# 16V3_EDA.net
KiCad netlist of a schematic drawn in EasyEDA Pro
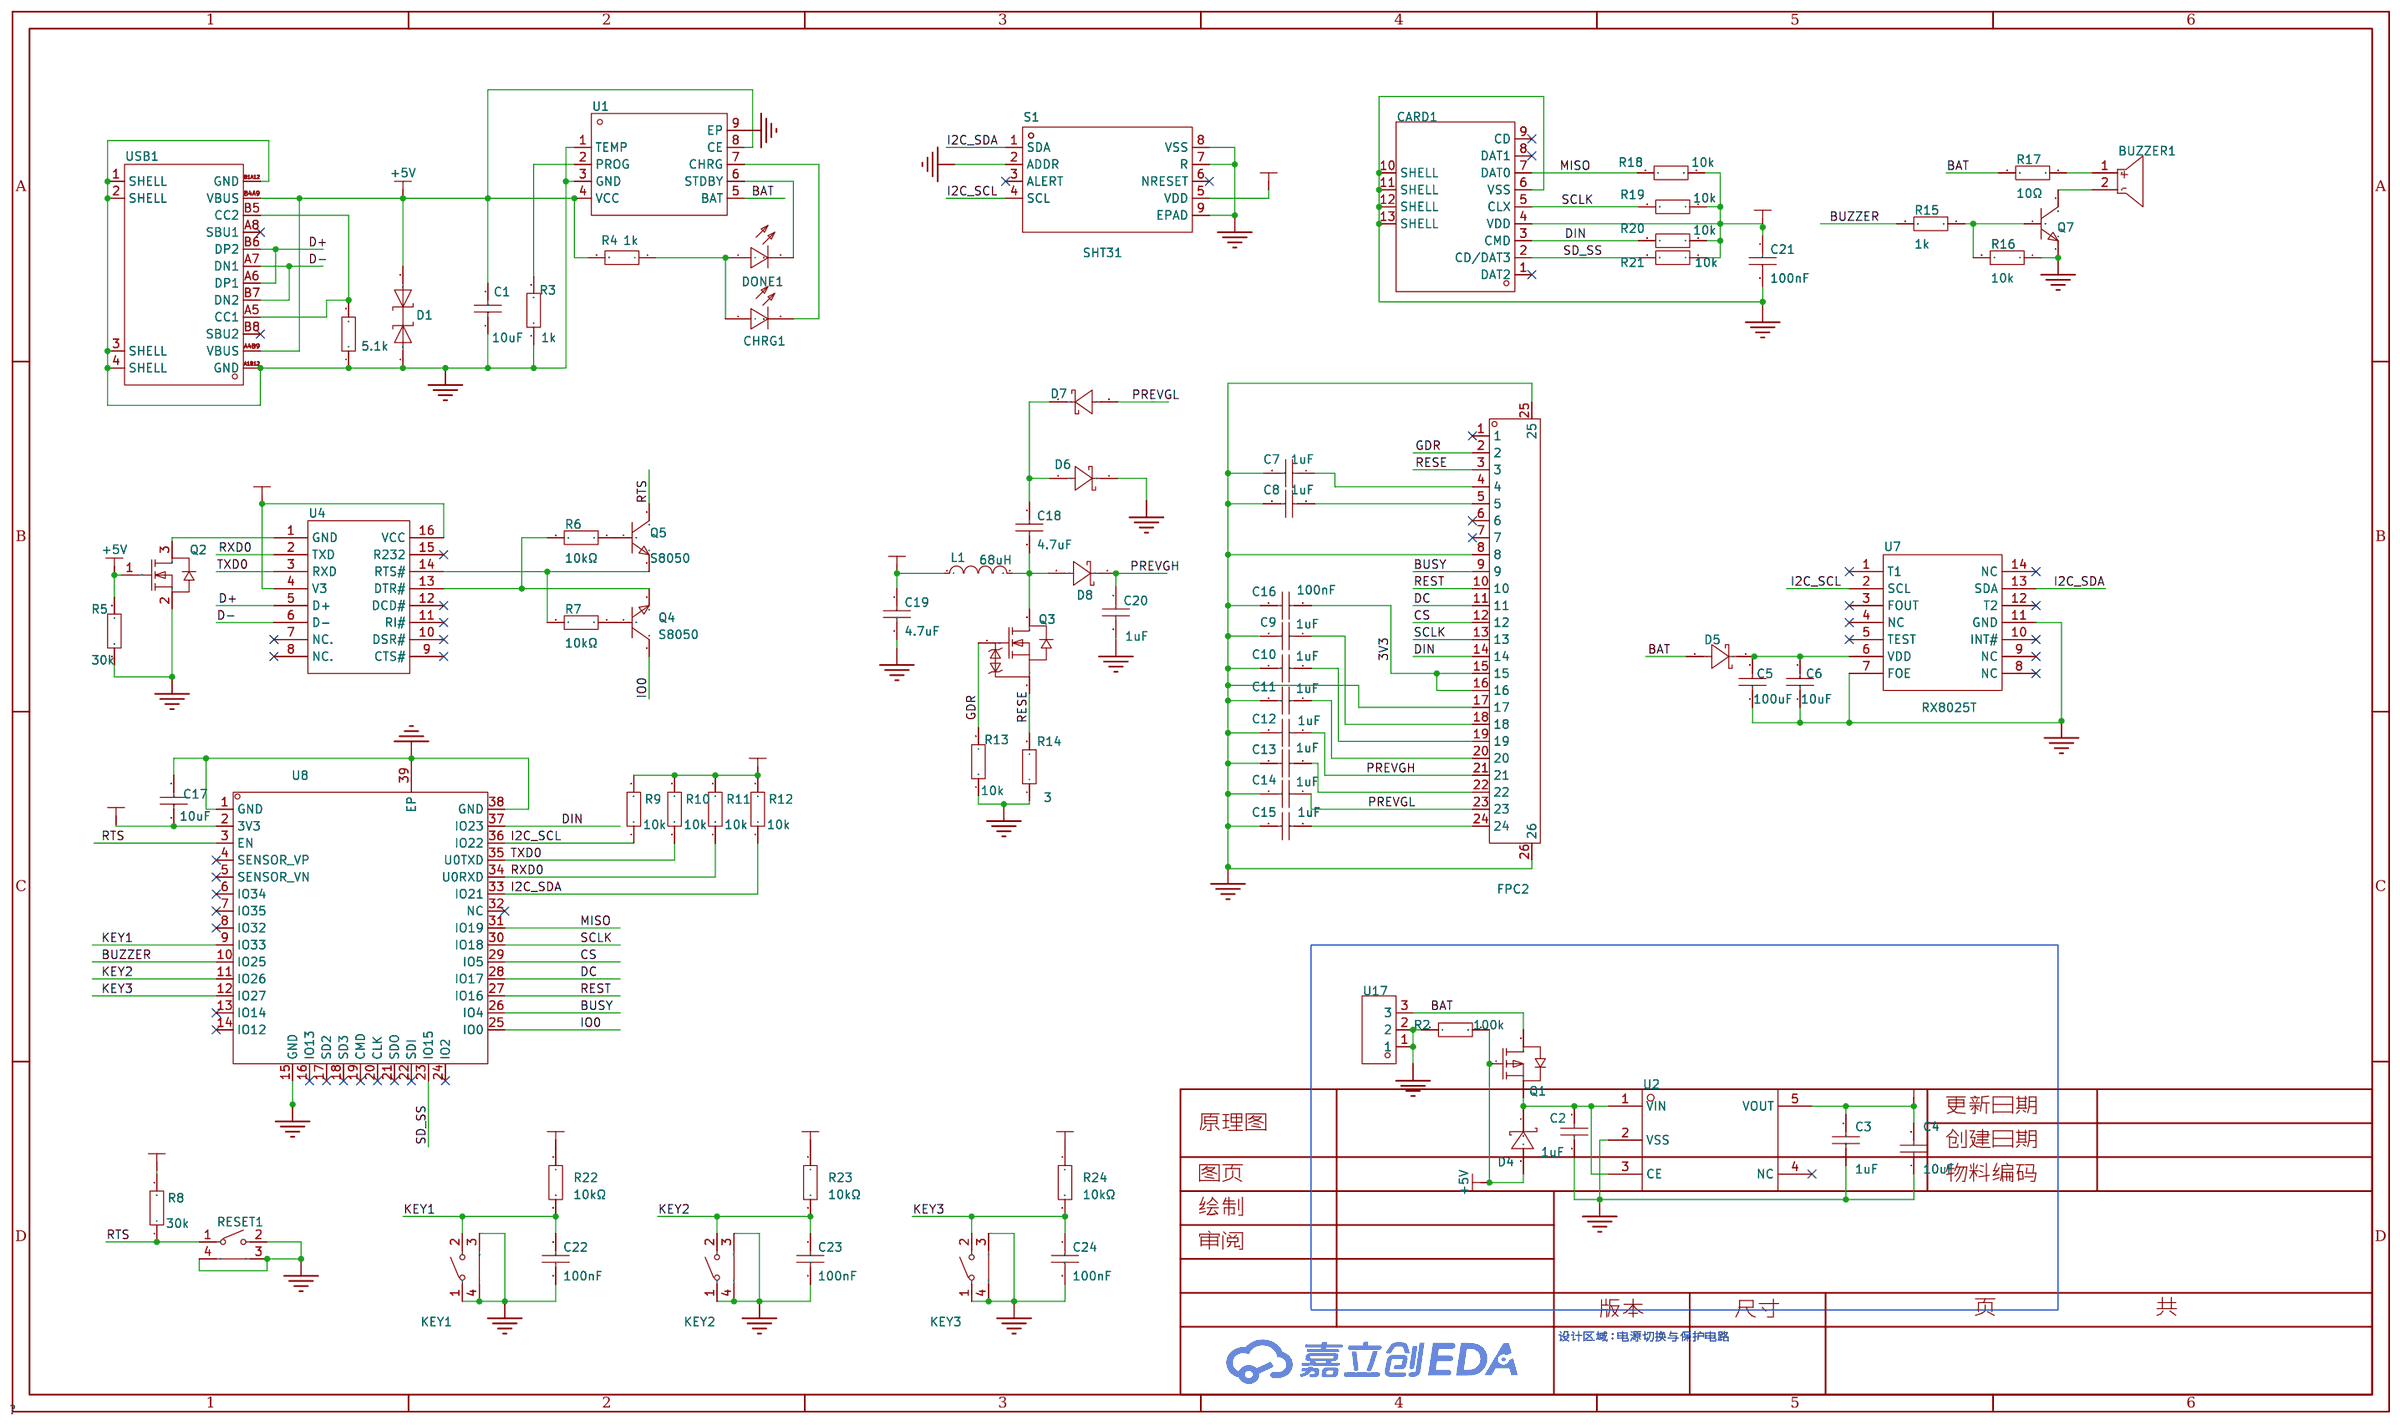
[diagram p0: schematic sheet]

(export (version "E")
  (design (tool "Eeschema 10.0.6"))
  (components
    (comp (ref "BUZZER1")
      (value "FMQ-BUZZER2")
      (footprint "easyedapro:BUZ-TH_BD12.0-P7.60-D0.6-FD")
      (libsource (lib "easyedapro") (part "FMQ-BUZZER2"))
    )
    (comp (ref "C1")
      (value "10uF")
      (footprint "easyedapro:C0805")
      (fields
        (field (name "Manufacturer Part") "CC0805KRX7R9BB104")
        (field (name "Manufacturer") "YAGEO(国巨)")
      )
      (libsource (lib "easyedapro") (part "CC0805KRX7R9BB104"))
    )
    (comp (ref "C2")
      (value "1uF")
      (footprint "easyedapro:C0805")
      (fields
        (field (name "Manufacturer Part") "CC0805KRX7R9BB104")
        (field (name "Manufacturer") "YAGEO(国巨)")
      )
      (libsource (lib "easyedapro") (part "CC0805KRX7R9BB104"))
    )
    (comp (ref "C3")
      (value "1uF")
      (footprint "easyedapro:C0805")
      (fields
        (field (name "Manufacturer Part") "CC0805KRX7R9BB104")
        (field (name "Manufacturer") "YAGEO(国巨)")
      )
      (libsource (lib "easyedapro") (part "CC0805KRX7R9BB104"))
    )
    (comp (ref "C4")
      (value "10uF")
      (footprint "easyedapro:C0805")
      (fields
        (field (name "Manufacturer Part") "CC0805KRX7R9BB104")
        (field (name "Manufacturer") "YAGEO(国巨)")
      )
      (libsource (lib "easyedapro") (part "CC0805KRX7R9BB104"))
    )
    (comp (ref "C5")
      (value "100uF")
      (footprint "easyedapro:C0805")
      (description "容值:100nF;精度:±10%;额定电压:50V;温度系数:X7R;")
      (fields
        (field (name "Manufacturer Part") "CC0805KRX7R9BB104")
        (field (name "Manufacturer") "YAGEO(国巨)")
      )
      (libsource (lib "easyedapro") (part "CC0805KRX7R9BB104"))
    )
    (comp (ref "C6")
      (value "10uF")
      (footprint "easyedapro:C0805")
      (fields
        (field (name "Manufacturer Part") "CC0805KRX7R9BB104")
        (field (name "Manufacturer") "YAGEO(国巨)")
      )
      (libsource (lib "easyedapro") (part "CC0805KRX7R9BB104"))
    )
    (comp (ref "C7")
      (value "1uF")
      (footprint "easyedapro:C0805")
      (fields
        (field (name "Manufacturer Part") "CC0805KRX7R9BB104")
        (field (name "Manufacturer") "YAGEO(国巨)")
      )
      (libsource (lib "easyedapro") (part "CC0805KRX7R9BB104"))
    )
    (comp (ref "C8")
      (value "1uF")
      (footprint "easyedapro:C0805")
      (fields
        (field (name "Manufacturer Part") "CC0805KRX7R9BB104")
        (field (name "Manufacturer") "YAGEO(国巨)")
      )
      (libsource (lib "easyedapro") (part "CC0805KRX7R9BB104"))
    )
    (comp (ref "C9")
      (value "1uF")
      (footprint "easyedapro:C0805")
      (fields
        (field (name "Manufacturer Part") "CC0805KRX7R9BB104")
        (field (name "Manufacturer") "YAGEO(国巨)")
      )
      (libsource (lib "easyedapro") (part "CC0805KRX7R9BB104"))
    )
    (comp (ref "C10")
      (value "1uF")
      (footprint "easyedapro:C0805")
      (fields
        (field (name "Manufacturer Part") "CC0805KRX7R9BB104")
        (field (name "Manufacturer") "YAGEO(国巨)")
      )
      (libsource (lib "easyedapro") (part "CC0805KRX7R9BB104"))
    )
    (comp (ref "C11")
      (value "1uF")
      (footprint "easyedapro:C0805")
      (fields
        (field (name "Manufacturer Part") "CC0805KRX7R9BB104")
        (field (name "Manufacturer") "YAGEO(国巨)")
      )
      (libsource (lib "easyedapro") (part "CC0805KRX7R9BB104"))
    )
    (comp (ref "C12")
      (value "1uF")
      (footprint "easyedapro:C0805")
      (fields
        (field (name "Manufacturer Part") "CC0805KRX7R9BB104")
        (field (name "Manufacturer") "YAGEO(国巨)")
      )
      (libsource (lib "easyedapro") (part "CC0805KRX7R9BB104"))
    )
    (comp (ref "C13")
      (value "1uF")
      (footprint "easyedapro:C0805")
      (fields
        (field (name "Manufacturer Part") "CC0805KRX7R9BB104")
        (field (name "Manufacturer") "YAGEO(国巨)")
      )
      (libsource (lib "easyedapro") (part "CC0805KRX7R9BB104"))
    )
    (comp (ref "C14")
      (value "1uF")
      (footprint "easyedapro:C0805")
      (fields
        (field (name "Manufacturer Part") "CC0805KRX7R9BB104")
        (field (name "Manufacturer") "YAGEO(国巨)")
      )
      (libsource (lib "easyedapro") (part "CC0805KRX7R9BB104"))
    )
    (comp (ref "C15")
      (value "1uF")
      (footprint "easyedapro:C0805")
      (fields
        (field (name "Manufacturer Part") "CC0805KRX7R9BB104")
        (field (name "Manufacturer") "YAGEO(国巨)")
      )
      (libsource (lib "easyedapro") (part "CC0805KRX7R9BB104"))
    )
    (comp (ref "C16")
      (value "100nF")
      (footprint "easyedapro:C0805")
      (description "容值:100nF;精度:±10%;额定电压:50V;温度系数:X7R;")
      (fields
        (field (name "Manufacturer Part") "CC0805KRX7R9BB104")
        (field (name "Manufacturer") "YAGEO(国巨)")
      )
      (libsource (lib "easyedapro") (part "CC0805KRX7R9BB104"))
    )
    (comp (ref "C17")
      (value "10uF")
      (footprint "easyedapro:C0805")
      (fields
        (field (name "Manufacturer Part") "CC0805KRX7R9BB104")
        (field (name "Manufacturer") "YAGEO(国巨)")
      )
      (libsource (lib "easyedapro") (part "CC0805KRX7R9BB104"))
    )
    (comp (ref "C18")
      (value "4.7uF")
      (footprint "easyedapro:C0805")
      (description "容值:100nF;精度:±10%;额定电压:50V;温度系数:X7R;")
      (fields
        (field (name "Manufacturer Part") "CC0805KRX7R9BB104")
        (field (name "Manufacturer") "YAGEO(国巨)")
      )
      (libsource (lib "easyedapro") (part "CC0805KRX7R9BB104"))
    )
    (comp (ref "C19")
      (value "4.7uF")
      (footprint "easyedapro:C0805")
      (fields
        (field (name "Manufacturer Part") "CC0805KRX7R9BB104")
        (field (name "Manufacturer") "YAGEO(国巨)")
      )
      (libsource (lib "easyedapro") (part "CC0805KRX7R9BB104"))
    )
    (comp (ref "C20")
      (value "1uF")
      (footprint "easyedapro:C0805")
      (fields
        (field (name "Manufacturer Part") "CC0805KRX7R9BB104")
        (field (name "Manufacturer") "YAGEO(国巨)")
      )
      (libsource (lib "easyedapro") (part "CC0805KRX7R9BB104"))
    )
    (comp (ref "C21")
      (value "100nF")
      (footprint "easyedapro:C0805")
      (description "容值:100nF;精度:±10%;额定电压:50V;温度系数:X7R;")
      (fields
        (field (name "Manufacturer Part") "CC0805KRX7R9BB104")
        (field (name "Manufacturer") "YAGEO(国巨)")
      )
      (libsource (lib "easyedapro") (part "CC0805KRX7R9BB104"))
    )
    (comp (ref "C22")
      (value "100nF")
      (footprint "easyedapro:C0805")
      (fields
        (field (name "Manufacturer Part") "CC0805KRX7R9BB104")
        (field (name "Manufacturer") "YAGEO(国巨)")
      )
      (libsource (lib "easyedapro") (part "CC0805KRX7R9BB104"))
    )
    (comp (ref "C23")
      (value "100nF")
      (footprint "easyedapro:C0805")
      (fields
        (field (name "Manufacturer Part") "CC0805KRX7R9BB104")
        (field (name "Manufacturer") "YAGEO(国巨)")
      )
      (libsource (lib "easyedapro") (part "CC0805KRX7R9BB104"))
    )
    (comp (ref "C24")
      (value "100nF")
      (footprint "easyedapro:C0805")
      (fields
        (field (name "Manufacturer Part") "CC0805KRX7R9BB104")
        (field (name "Manufacturer") "YAGEO(国巨)")
      )
      (libsource (lib "easyedapro") (part "CC0805KRX7R9BB104"))
    )
    (comp (ref "CARD1")
      (value "~")
      (footprint "easyedapro:TF-SMD_THD2528-11SD-GF")
      (description "卡连接方式:自弹式;卡类型:MicroSD卡(TF卡);连接器类型:卡座;本体最大高度:2mm;工作温度范围:-;")
      (fields (field (name "Manufacturer Part") "THD2528-11SD-GF") (field (name "Manufacturer") "THD(台华达)"))
      (libsource (lib "easyedapro") (part "THD2528-11SD-GF"))
    )
    (comp (ref "CHRG1")
      (value "~")
      (footprint "easyedapro:LED0603-R-RD")
      (fields
        (field (name "Manufacturer Part") "19-217/R6C-AL1M2VY/3T")
        (field (name "Manufacturer") "EVERLIGHT(台湾亿光)")
      )
      (libsource (lib "easyedapro") (part "19-217/R6C-AL1M2VY/3T"))
    )
    (comp (ref "D1")
      (value "~")
      (footprint "easyedapro:SOD-523_L1.2-W0.8-LS1.6-BI")
      (description "极性:双向;反向截止电压(Vrwm):5V@(最大值);击穿电压(最小值):5.6V;峰值脉冲电流(Ipp)@10/1000s:4A;最大钳位电压:12V;")
      (fields (field (name "Manufacturer Part") "ESD5Z5.0VC") (field (name "Manufacturer") "TC(德昌)"))
      (libsource (lib "easyedapro") (part "ESD5Z5.0VC"))
    )
    (comp (ref "D4")
      (value "~")
      (footprint "easyedapro:SMA_L4.3-W2.6-LS5.1-RD")
      (description "直流反向耐压(Vr):40V;平均整流电流(Io):3A;正向压降(Vf):550mV@3A;")
      (fields (field (name "Manufacturer Part") "SS34") (field (name "Manufacturer") "SINO-IC(光宇睿芯)"))
      (libsource (lib "easyedapro") (part "SS34_C355267"))
    )
    (comp (ref "D5")
      (value "~")
      (footprint "easyedapro:SOD-123_L2.7-W1.6-LS3.7-RD-1")
      (description "直流反向耐压(Vr):30V;平均整流电流(Io):500mA;正向压降(Vf):550mV@500mA;")
      (fields (field (name "Manufacturer Part") "MBR0530") (field (name "Manufacturer") "YANGJIE(扬杰)"))
      (libsource (lib "easyedapro") (part "MBR0530_C699108"))
    )
    (comp (ref "D6")
      (value "~")
      (footprint "easyedapro:SOD-123_L2.7-W1.6-LS3.7-RD-1")
      (description "直流反向耐压(Vr):30V;平均整流电流(Io):500mA;正向压降(Vf):550mV@500mA;")
      (fields (field (name "Manufacturer Part") "MBR0530") (field (name "Manufacturer") "YANGJIE(扬杰)"))
      (libsource (lib "easyedapro") (part "MBR0530_C699108"))
    )
    (comp (ref "D7")
      (value "~")
      (footprint "easyedapro:SOD-123_L2.7-W1.6-LS3.7-RD-1")
      (description "直流反向耐压(Vr):30V;平均整流电流(Io):500mA;正向压降(Vf):550mV@500mA;")
      (fields (field (name "Manufacturer Part") "MBR0530") (field (name "Manufacturer") "YANGJIE(扬杰)"))
      (libsource (lib "easyedapro") (part "MBR0530_C699108"))
    )
    (comp (ref "D8")
      (value "~")
      (footprint "easyedapro:SOD-123_L2.7-W1.6-LS3.7-RD-1")
      (description "直流反向耐压(Vr):30V;平均整流电流(Io):500mA;正向压降(Vf):550mV@500mA;")
      (fields (field (name "Manufacturer Part") "MBR0530") (field (name "Manufacturer") "YANGJIE(扬杰)"))
      (libsource (lib "easyedapro") (part "MBR0530_C699108"))
    )
    (comp (ref "DONE1")
      (value "~")
      (footprint "easyedapro:LED0603-R-RD")
      (fields
        (field (name "Manufacturer Part") "19-217/R6C-AL1M2VY/3T")
        (field (name "Manufacturer") "EVERLIGHT(台湾亿光)")
      )
      (libsource (lib "easyedapro") (part "19-217/R6C-AL1M2VY/3T"))
    )
    (comp (ref "FPC2")
      (value "~")
      (footprint "easyedapro:FPC-SMD_24P-L17.5-W5.4-P0.50")
      (description "间距:0.5mm;触点数量:24;锁定特性:抽屉式;安装类型:卧贴;触点类型:上接;")
      (fields (field (name "Manufacturer Part") "AFC07-S24ECC-00") (field (name "Manufacturer") "JS(钜硕电子)"))
      (libsource (lib "easyedapro") (part "FPC 0.5MM 24P Pull type H2.0mm Pick up"))
    )
    (comp (ref "KEY1")
      (value "~")
      (footprint "easyedapro:SW-SMD_L4.7-W3.5-P3.35-EH")
      (fields
        (field (name "Manufacturer Part") "GT-TC018B-H0375-L1")
        (field (name "Manufacturer") "G-Switch(品赞)")
      )
      (libsource (lib "easyedapro") (part "GT-TC018B-H0375-L1"))
    )
    (comp (ref "KEY2")
      (value "~")
      (footprint "easyedapro:SW-SMD_L4.7-W3.5-P3.35-EH")
      (fields
        (field (name "Manufacturer Part") "GT-TC018B-H0375-L1")
        (field (name "Manufacturer") "G-Switch(品赞)")
      )
      (libsource (lib "easyedapro") (part "GT-TC018B-H0375-L1"))
    )
    (comp (ref "KEY3")
      (value "~")
      (footprint "easyedapro:SW-SMD_L4.7-W3.5-P3.35-EH")
      (fields
        (field (name "Manufacturer Part") "GT-TC018B-H0375-L1")
        (field (name "Manufacturer") "G-Switch(品赞)")
      )
      (libsource (lib "easyedapro") (part "GT-TC018B-H0375-L1"))
    )
    (comp (ref "L1")
      (value "68uH")
      (footprint "easyedapro:IND-SMD_L4.0-W4.0")
      (description "电感值:68uH;精度:±20%;额定电流:-;直流电阻(DCR):-;")
      (fields (field (name "Manufacturer Part") "CR4020-680M") (field (name "Manufacturer") "ceaiya(柯爱亚)"))
      (libsource (lib "easyedapro") (part "CR4020-680M"))
    )
    (comp (ref "Q1")
      (value "~")
      (footprint "easyedapro:SOT-23_L2.9-W1.3-P1.90-LS2.4-BR")
      (fields (field (name "Manufacturer Part") "SI2305") (field (name "Manufacturer") "BORN伯恩半导体"))
      (libsource (lib "easyedapro") (part "SI2305_C344006"))
    )
    (comp (ref "Q2")
      (value "~")
      (footprint "easyedapro:SOT-23_L2.9-W1.3-P1.90-LS2.4-BR")
      (fields (field (name "Manufacturer Part") "AO3402") (field (name "Manufacturer") "GOODWORK(固得沃克)"))
      (libsource (lib "easyedapro") (part "AO3402_C2938369"))
    )
    (comp (ref "Q3")
      (value "~")
      (footprint "easyedapro:SOT-323_L2.0-W1.3-P1.30-LS2.1-BR")
      (fields
        (field (name "Manufacturer Part") "SI1308EDL-T1-GE3")
        (field (name "Manufacturer") "VISHAY(威世)")
      )
      (libsource (lib "easyedapro") (part "SI1308EDL-T1-GE3"))
    )
    (comp (ref "Q4")
      (value "S8050")
      (footprint "easyedapro:SOT-23-3_L3.0-W1.7-P0.95-LS2.9-BR")
      (fields (field (name "Manufacturer") "CJ"))
      (libsource (lib "") (part "S8050_1"))
    )
    (comp (ref "Q5")
      (value "S8050")
      (footprint "easyedapro:SOT-23-3_L3.0-W1.7-P0.95-LS2.9-BR(1)")
      (fields (field (name "Manufacturer") "CJ"))
      (libsource (lib "easyedapro") (part "S8050"))
    )
    (comp (ref "Q7")
      (value "S8050-J3Y")
      (footprint "easyedapro:SOT-23-3_L3.0-W1.7-P0.95-LS2.9-BR")
      (fields (field (name "Manufacturer") "(MDD) Jiangsu Yutai Elec"))
      (libsource (lib "easyedapro") (part "S8050-J3Y"))
    )
    (comp (ref "R1")
      (value "5.1k")
      (footprint "easyedapro:R0603")
      (description "电阻类型:薄膜电阻;阻值:10k;精度:±0.1%;功率:100mW;温度系数:±25ppm/;最大工作电压:75V;工作温度范围:-55~+155;")
      (fields
        (field (name "Manufacturer Part") "TR0603B10K0P0525Z")
        (field (name "Manufacturer") "EVER OHMS(天二科技)")
      )
      (libsource (lib "easyedapro") (part "TR0603B10KP05250.1W"))
    )
    (comp (ref "R2")
      (value "100k")
      (footprint "easyedapro:R0603")
      (description "电阻类型:薄膜电阻;阻值:10k;精度:±0.1%;功率:100mW;温度系数:±25ppm/;最大工作电压:75V;工作温度范围:-55~+155;")
      (fields
        (field (name "Manufacturer Part") "TR0603B10K0P0525Z")
        (field (name "Manufacturer") "EVER OHMS(天二科技)")
      )
      (libsource (lib "easyedapro") (part "TR0603B10KP05250.1W"))
    )
    (comp (ref "R3")
      (value "1k")
      (footprint "easyedapro:R0603")
      (description "电阻类型:薄膜电阻;阻值:10k;精度:±0.1%;功率:100mW;温度系数:±25ppm/;最大工作电压:75V;工作温度范围:-55~+155;")
      (fields
        (field (name "Manufacturer Part") "TR0603B10K0P0525Z")
        (field (name "Manufacturer") "EVER OHMS(天二科技)")
      )
      (libsource (lib "easyedapro") (part "TR0603B10KP05250.1W"))
    )
    (comp (ref "R4")
      (value "1k")
      (footprint "easyedapro:R0603")
      (description "电阻类型:薄膜电阻;阻值:10k;精度:±0.1%;功率:100mW;温度系数:±25ppm/;最大工作电压:75V;工作温度范围:-55~+155;")
      (fields
        (field (name "Manufacturer Part") "TR0603B10K0P0525Z")
        (field (name "Manufacturer") "EVER OHMS(天二科技)")
      )
      (libsource (lib "easyedapro") (part "TR0603B10KP05250.1W"))
    )
    (comp (ref "R5")
      (value "30k")
      (footprint "easyedapro:R0603")
      (description "电阻类型:薄膜电阻;阻值:10k;精度:±0.1%;功率:100mW;温度系数:±25ppm/;最大工作电压:75V;工作温度范围:-55~+155;")
      (fields
        (field (name "Manufacturer Part") "TR0603B10K0P0525Z")
        (field (name "Manufacturer") "EVER OHMS(天二科技)")
      )
      (libsource (lib "easyedapro") (part "TR0603B10KP05250.1W"))
    )
    (comp (ref "R6")
      (value "10kΩ")
      (footprint "easyedapro:R0603")
      (description "电阻类型:薄膜电阻;阻值:10k;精度:±0.1%;功率:100mW;温度系数:±25ppm/;最大工作电压:75V;工作温度范围:-55~+155;")
      (fields
        (field (name "Manufacturer Part") "TR0603B10K0P0525Z")
        (field (name "Manufacturer") "EVER OHMS(天二科技)")
      )
      (libsource (lib "easyedapro") (part "TR0603B10KP05250.1W"))
    )
    (comp (ref "R7")
      (value "10kΩ")
      (footprint "easyedapro:R0603")
      (description "电阻类型:薄膜电阻;阻值:10k;精度:±0.1%;功率:100mW;温度系数:±25ppm/;最大工作电压:75V;工作温度范围:-55~+155;")
      (fields
        (field (name "Manufacturer Part") "TR0603B10K0P0525Z")
        (field (name "Manufacturer") "EVER OHMS(天二科技)")
      )
      (libsource (lib "easyedapro") (part "TR0603B10KP05250.1W"))
    )
    (comp (ref "R8")
      (value "30k")
      (footprint "easyedapro:R0603")
      (description "电阻类型:薄膜电阻;阻值:10k;精度:±0.1%;功率:100mW;温度系数:±25ppm/;最大工作电压:75V;工作温度范围:-55~+155;")
      (fields
        (field (name "Manufacturer Part") "TR0603B10K0P0525Z")
        (field (name "Manufacturer") "EVER OHMS(天二科技)")
      )
      (libsource (lib "easyedapro") (part "TR0603B10KP05250.1W"))
    )
    (comp (ref "R9")
      (value "10k")
      (footprint "easyedapro:R0603")
      (description "电阻类型:薄膜电阻;阻值:10k;精度:±0.1%;功率:100mW;温度系数:±25ppm/;最大工作电压:75V;工作温度范围:-55~+155;")
      (fields
        (field (name "Manufacturer Part") "TR0603B10K0P0525Z")
        (field (name "Manufacturer") "EVER OHMS(天二科技)")
      )
      (libsource (lib "easyedapro") (part "TR0603B10KP05250.1W"))
    )
    (comp (ref "R10")
      (value "10k")
      (footprint "easyedapro:R0603")
      (description "电阻类型:薄膜电阻;阻值:10k;精度:±0.1%;功率:100mW;温度系数:±25ppm/;最大工作电压:75V;工作温度范围:-55~+155;")
      (fields
        (field (name "Manufacturer Part") "TR0603B10K0P0525Z")
        (field (name "Manufacturer") "EVER OHMS(天二科技)")
      )
      (libsource (lib "easyedapro") (part "TR0603B10KP05250.1W"))
    )
    (comp (ref "R11")
      (value "10k")
      (footprint "easyedapro:R0603")
      (description "电阻类型:薄膜电阻;阻值:10k;精度:±0.1%;功率:100mW;温度系数:±25ppm/;最大工作电压:75V;工作温度范围:-55~+155;")
      (fields
        (field (name "Manufacturer Part") "TR0603B10K0P0525Z")
        (field (name "Manufacturer") "EVER OHMS(天二科技)")
      )
      (libsource (lib "easyedapro") (part "TR0603B10KP05250.1W"))
    )
    (comp (ref "R12")
      (value "10k")
      (footprint "easyedapro:R0603")
      (description "电阻类型:薄膜电阻;阻值:10k;精度:±0.1%;功率:100mW;温度系数:±25ppm/;最大工作电压:75V;工作温度范围:-55~+155;")
      (fields
        (field (name "Manufacturer Part") "TR0603B10K0P0525Z")
        (field (name "Manufacturer") "EVER OHMS(天二科技)")
      )
      (libsource (lib "easyedapro") (part "TR0603B10KP05250.1W"))
    )
    (comp (ref "R13")
      (value "10k")
      (footprint "easyedapro:R0603")
      (description "电阻类型:薄膜电阻;阻值:10k;精度:±0.1%;功率:100mW;温度系数:±25ppm/;最大工作电压:75V;工作温度范围:-55~+155;")
      (fields
        (field (name "Manufacturer Part") "TR0603B10K0P0525Z")
        (field (name "Manufacturer") "EVER OHMS(天二科技)")
      )
      (libsource (lib "easyedapro") (part "TR0603B10KP05250.1W"))
    )
    (comp (ref "R14")
      (value "3")
      (footprint "easyedapro:R0603")
      (description "电阻类型:薄膜电阻;阻值:10k;精度:±0.1%;功率:100mW;温度系数:±25ppm/;最大工作电压:75V;工作温度范围:-55~+155;")
      (fields
        (field (name "Manufacturer Part") "TR0603B10K0P0525Z")
        (field (name "Manufacturer") "EVER OHMS(天二科技)")
      )
      (libsource (lib "easyedapro") (part "TR0603B10KP05250.1W"))
    )
    (comp (ref "R15")
      (value "1k")
      (footprint "easyedapro:R0603")
      (description "电阻类型:薄膜电阻;阻值:10k;精度:±0.1%;功率:100mW;温度系数:±25ppm/;最大工作电压:75V;工作温度范围:-55~+155;")
      (fields
        (field (name "Manufacturer Part") "TR0603B10K0P0525Z")
        (field (name "Manufacturer") "EVER OHMS(天二科技)")
      )
      (libsource (lib "easyedapro") (part "TR0603B10KP05250.1W"))
    )
    (comp (ref "R16")
      (value "10k")
      (footprint "easyedapro:R0603")
      (description "电阻类型:薄膜电阻;阻值:10k;精度:±0.1%;功率:100mW;温度系数:±25ppm/;最大工作电压:75V;工作温度范围:-55~+155;")
      (fields
        (field (name "Manufacturer Part") "TR0603B10K0P0525Z")
        (field (name "Manufacturer") "EVER OHMS(天二科技)")
      )
      (libsource (lib "easyedapro") (part "TR0603B10KP05250.1W"))
    )
    (comp (ref "R17")
      (value "10Ω")
      (footprint "easyedapro:R0603")
      (description "电阻类型:厚膜电阻;阻值:10Ω;精度:±1%;功率:100mW;")
      (fields
        (field (name "Manufacturer Part") "0603WAF100JT5E")
        (field (name "Manufacturer") "UNI-ROYAL(厚声)")
      )
      (libsource (lib "easyedapro") (part "0603WAF100JT5E"))
    )
    (comp (ref "R18")
      (value "10k")
      (footprint "easyedapro:R0603")
      (description "电阻类型:薄膜电阻;阻值:10k;精度:±0.1%;功率:100mW;温度系数:±25ppm/;最大工作电压:75V;工作温度范围:-55~+155;")
      (fields
        (field (name "Manufacturer Part") "TR0603B10K0P0525Z")
        (field (name "Manufacturer") "EVER OHMS(天二科技)")
      )
      (libsource (lib "easyedapro") (part "TR0603B10KP05250.1W"))
    )
    (comp (ref "R19")
      (value "10k")
      (footprint "easyedapro:R0603")
      (description "电阻类型:薄膜电阻;阻值:10k;精度:±0.1%;功率:100mW;温度系数:±25ppm/;最大工作电压:75V;工作温度范围:-55~+155;")
      (fields
        (field (name "Manufacturer Part") "TR0603B10K0P0525Z")
        (field (name "Manufacturer") "EVER OHMS(天二科技)")
      )
      (libsource (lib "easyedapro") (part "TR0603B10KP05250.1W"))
    )
    (comp (ref "R20")
      (value "10k")
      (footprint "easyedapro:R0603")
      (description "电阻类型:薄膜电阻;阻值:10k;精度:±0.1%;功率:100mW;温度系数:±25ppm/;最大工作电压:75V;工作温度范围:-55~+155;")
      (fields
        (field (name "Manufacturer Part") "TR0603B10K0P0525Z")
        (field (name "Manufacturer") "EVER OHMS(天二科技)")
      )
      (libsource (lib "easyedapro") (part "TR0603B10KP05250.1W"))
    )
    (comp (ref "R21")
      (value "10k")
      (footprint "easyedapro:R0603")
      (description "电阻类型:薄膜电阻;阻值:10k;精度:±0.1%;功率:100mW;温度系数:±25ppm/;最大工作电压:75V;工作温度范围:-55~+155;")
      (fields
        (field (name "Manufacturer Part") "TR0603B10K0P0525Z")
        (field (name "Manufacturer") "EVER OHMS(天二科技)")
      )
      (libsource (lib "easyedapro") (part "TR0603B10KP05250.1W"))
    )
    (comp (ref "R22")
      (value "10kΩ")
      (footprint "easyedapro:R0603")
      (description "电阻类型:薄膜电阻;阻值:10k;精度:±0.1%;功率:100mW;温度系数:±25ppm/;最大工作电压:75V;工作温度范围:-55~+155;")
      (fields
        (field (name "Manufacturer Part") "TR0603B10K0P0525Z")
        (field (name "Manufacturer") "EVER OHMS(天二科技)")
      )
      (libsource (lib "easyedapro") (part "TR0603B10KP05250.1W"))
    )
    (comp (ref "R23")
      (value "10kΩ")
      (footprint "easyedapro:R0603")
      (description "电阻类型:薄膜电阻;阻值:10k;精度:±0.1%;功率:100mW;温度系数:±25ppm/;最大工作电压:75V;工作温度范围:-55~+155;")
      (fields
        (field (name "Manufacturer Part") "TR0603B10K0P0525Z")
        (field (name "Manufacturer") "EVER OHMS(天二科技)")
      )
      (libsource (lib "easyedapro") (part "TR0603B10KP05250.1W"))
    )
    (comp (ref "R24")
      (value "10kΩ")
      (footprint "easyedapro:R0603")
      (description "电阻类型:薄膜电阻;阻值:10k;精度:±0.1%;功率:100mW;温度系数:±25ppm/;最大工作电压:75V;工作温度范围:-55~+155;")
      (fields
        (field (name "Manufacturer Part") "TR0603B10K0P0525Z")
        (field (name "Manufacturer") "EVER OHMS(天二科技)")
      )
      (libsource (lib "easyedapro") (part "TR0603B10KP05250.1W"))
    )
    (comp (ref "RESET1")
      (value "~")
      (footprint "easyedapro:SW-SMD_L4.7-W3.5-P3.35-EH")
      (fields
        (field (name "Manufacturer Part") "GT-TC018B-H0375-L1")
        (field (name "Manufacturer") "G-Switch(品赞)")
      )
      (libsource (lib "easyedapro") (part "GT-TC018B-H0375-L1"))
    )
    (comp (ref "S1")
      (value "SHT31")
      (footprint "easyedapro:DFN-8_L2.5-W2.5-P0.50-BL-EP")
      (description "1-101386-01")
      (fields (field (name "Manufacturer") "Sensirion(瑞士盛思锐)"))
      (libsource (lib "easyedapro") (part "SHT31-DIS-B"))
    )
    (comp (ref "U1")
      (value "~")
      (footprint "easyedapro:ESOP-8_L4.9-W3.9-P1.27-LS6.0-BL-EP")
      (description "充电电池的类型:-;电池单元组数:-;最大充电电流:-;充满的电池组电压:-;最大供应电压:-;")
      (fields (field (name "Manufacturer Part") "TP4056") (field (name "Manufacturer") "UMW(友台半导体)"))
      (libsource (lib "easyedapro") (part "TP4056_C725790"))
    )
    (comp (ref "U2") (value "~") (libsource (lib "easyedapro") (part "LDO")))
    (comp (ref "U4")
      (value "~")
      (footprint "easyedapro:SOP-16_L10.0-W3.9-P1.27-LS6.0-BL")
      (description "类型:Transceiver;协议类别:USB 2.0;驱动器/接收器数:-;数据速率:2Mbps;")
      (fields (field (name "Manufacturer Part") "CH340C") (field (name "Manufacturer") "WCH(南京沁恒)"))
      (libsource (lib "easyedapro") (part "CH340C"))
    )
    (comp (ref "U7")
      (value "RX8025T")
      (footprint "easyedapro:SOIC-14_L10.0-W5.5-P1.27-LS7.8-BL")
      (description "时钟芯片类型:Clock/Calendar;存储器容量:-;时间格式:HH:MM:SS;日期格式:YY-MM-DD;接口类型:I2C;")
      (fields (field (name "Manufacturer Part") "RX8025T-UB") (field (name "Manufacturer") "EPSON(爱普生)"))
      (libsource (lib "easyedapro") (part "RX8025T-UB"))
    )
    (comp (ref "U8")
      (value "~")
      (footprint "easyedapro:WIRELM-SMD_ESP32-S")
      (fields (field (name "Manufacturer Part") "ESP32-S") (field (name "Manufacturer") "Ai-Thinker(安信可)"))
      (libsource (lib "easyedapro") (part "ESP32-S"))
    )
    (comp (ref "U17")
      (value "ZX-XH2.54-3PZZ")
      (footprint "easyedapro:CONN-TH_3P-P2.54_2501S-3P")
      (fields (field (name "Manufacturer") "Megastar(兆星)"))
      (libsource (lib "easyedapro") (part "ZX-XH2.54-3PZZ"))
    )
    (comp (ref "USB1")
      (value "~")
      (footprint "easyedapro:USB-SMD_TYPE-611S-T3")
      (description "连接器类型:Type-C;标准:-;公母:母座;触点数量:16;端口数量:1;安装方式:卧贴;额定电流 - 电源:3A;工作温度范围:-25~+85;")
      (fields (field (name "Manufacturer Part") "TYPE-611S-T3") (field (name "Manufacturer") "Yuandi(台湾元迪)"))
      (libsource (lib "easyedapro") (part "TYPE-611S-T3"))
    )
  )
  (nets
    (net (code "1") (name "+5V") (class "Default")
      (node (ref "C1") (pin "2") (pinfunction "2_2") (pintype "input"))
      (node (ref "D1") (pin "2") (pinfunction "2_2") (pintype "input"))
      (node (ref "D4") (pin "2") (pinfunction "A_2") (pintype "input"))
      (node (ref "Q1") (pin "1") (pinfunction "G_1") (pintype "input"))
      (node (ref "Q2") (pin "1") (pinfunction "G_1") (pintype "input"))
      (node (ref "R2") (pin "2") (pinfunction "2_2") (pintype "input"))
      (node (ref "R4") (pin "2") (pinfunction "2_2") (pintype "input"))
      (node (ref "R5") (pin "2") (pinfunction "2_2") (pintype "input"))
      (node (ref "U1") (pin "4") (pinfunction "VCC_4") (pintype "input"))
      (node (ref "U1") (pin "8") (pinfunction "CE_8") (pintype "input"))
      (node (ref "USB1") (pin "A4B9") (pinfunction "VBUS_A4B9") (pintype "input"))
      (node (ref "USB1") (pin "B4A9") (pinfunction "VBUS_B4A9") (pintype "input"))
    )
    (net (code "2") (name "/BAT") (class "Default")
      (node (ref "D5") (pin "2") (pinfunction "A_2") (pintype "input"))
      (node (ref "Q1") (pin "3") (pinfunction "D_3") (pintype "input"))
      (node (ref "R17") (pin "1") (pinfunction "1_1") (pintype "input"))
      (node (ref "U1") (pin "5") (pinfunction "BAT_5") (pintype "input"))
      (node (ref "U17") (pin "3") (pinfunction "3_3") (pintype "unspecified"))
    )
    (net (code "3") (name "/BUSY") (class "Default")
      (node (ref "FPC2") (pin "9") (pinfunction "9_9") (pintype "input"))
      (node (ref "U8") (pin "26") (pinfunction "IO4_26") (pintype "input"))
    )
    (net (code "4") (name "/BUZZER") (class "Default")
      (node (ref "R15") (pin "2") (pinfunction "2_2") (pintype "input"))
      (node (ref "U8") (pin "10") (pinfunction "IO25_10") (pintype "input"))
    )
    (net (code "5") (name "/CS") (class "Default")
      (node (ref "FPC2") (pin "12") (pinfunction "12_12") (pintype "input"))
      (node (ref "U8") (pin "29") (pinfunction "IO5_29") (pintype "input"))
    )
    (net (code "6") (name "/D+") (class "Default")
      (node (ref "U4") (pin "5") (pinfunction "D+_5") (pintype "input"))
      (node (ref "USB1") (pin "A6") (pinfunction "DP1_A6") (pintype "input"))
      (node (ref "USB1") (pin "B6") (pinfunction "DP2_B6") (pintype "input"))
    )
    (net (code "7") (name "/D-") (class "Default")
      (node (ref "U4") (pin "6") (pinfunction "D-_6") (pintype "input"))
      (node (ref "USB1") (pin "A7") (pinfunction "DN1_A7") (pintype "input"))
      (node (ref "USB1") (pin "B7") (pinfunction "DN2_B7") (pintype "input"))
    )
    (net (code "8") (name "/DC") (class "Default")
      (node (ref "FPC2") (pin "11") (pinfunction "11_11") (pintype "input"))
      (node (ref "U8") (pin "28") (pinfunction "IO17_28") (pintype "input"))
    )
    (net (code "9") (name "/DIN") (class "Default")
      (node (ref "CARD1") (pin "3") (pinfunction "CMD_3") (pintype "input"))
      (node (ref "FPC2") (pin "14") (pinfunction "14_14") (pintype "input"))
      (node (ref "R20") (pin "2") (pinfunction "2_2") (pintype "input"))
      (node (ref "U8") (pin "37") (pinfunction "IO23_37") (pintype "input"))
    )
    (net (code "10") (name "/GDR") (class "Default")
      (node (ref "FPC2") (pin "2") (pinfunction "2_2") (pintype "input"))
      (node (ref "Q3") (pin "1") (pinfunction "G_1") (pintype "input"))
      (node (ref "R13") (pin "2") (pinfunction "2_2") (pintype "input"))
    )
    (net (code "11") (name "/I2C_SCL") (class "Default")
      (node (ref "R9") (pin "1") (pinfunction "1_1") (pintype "input"))
      (node (ref "S1") (pin "4") (pinfunction "SCL_4") (pintype "unspecified"))
      (node (ref "U7") (pin "2") (pinfunction "SCL_2") (pintype "input"))
      (node (ref "U8") (pin "36") (pinfunction "IO22_36") (pintype "input"))
    )
    (net (code "12") (name "/I2C_SDA") (class "Default")
      (node (ref "R12") (pin "1") (pinfunction "1_1") (pintype "input"))
      (node (ref "S1") (pin "1") (pinfunction "SDA_1") (pintype "unspecified"))
      (node (ref "U7") (pin "13") (pinfunction "SDA_13") (pintype "input"))
      (node (ref "U8") (pin "33") (pinfunction "IO21_33") (pintype "input"))
    )
    (net (code "13") (name "/IO0") (class "Default")
      (node (ref "Q4") (pin "3") (pinfunction "C_3") (pintype "input"))
      (node (ref "U8") (pin "25") (pinfunction "IO0_25") (pintype "input"))
    )
    (net (code "14") (name "/KEY1") (class "Default")
      (node (ref "C22") (pin "1") (pinfunction "1_1") (pintype "input"))
      (node (ref "KEY1") (pin "2") (pinfunction "2_2") (pintype "input"))
      (node (ref "R22") (pin "2") (pinfunction "2_2") (pintype "input"))
      (node (ref "U8") (pin "9") (pinfunction "IO33_9") (pintype "input"))
    )
    (net (code "15") (name "/KEY2") (class "Default")
      (node (ref "C23") (pin "1") (pinfunction "1_1") (pintype "input"))
      (node (ref "KEY2") (pin "2") (pinfunction "2_2") (pintype "input"))
      (node (ref "R23") (pin "2") (pinfunction "2_2") (pintype "input"))
      (node (ref "U8") (pin "11") (pinfunction "IO26_11") (pintype "input"))
    )
    (net (code "16") (name "/KEY3") (class "Default")
      (node (ref "C24") (pin "1") (pinfunction "1_1") (pintype "input"))
      (node (ref "KEY3") (pin "2") (pinfunction "2_2") (pintype "input"))
      (node (ref "R24") (pin "2") (pinfunction "2_2") (pintype "input"))
      (node (ref "U8") (pin "12") (pinfunction "IO27_12") (pintype "input"))
    )
    (net (code "17") (name "/MISO") (class "Default")
      (node (ref "CARD1") (pin "7") (pinfunction "DAT0_7") (pintype "input"))
      (node (ref "R18") (pin "2") (pinfunction "2_2") (pintype "input"))
      (node (ref "U8") (pin "31") (pinfunction "IO19_31") (pintype "input"))
    )
    (net (code "18") (name "/PREVGH") (class "Default")
      (node (ref "C12") (pin "1") (pinfunction "1_1") (pintype "input"))
      (node (ref "C20") (pin "1") (pinfunction "1_1") (pintype "input"))
      (node (ref "D8") (pin "1") (pinfunction "K_1") (pintype "input"))
      (node (ref "FPC2") (pin "21") (pinfunction "21_21") (pintype "input"))
    )
    (net (code "19") (name "/PREVGL") (class "Default")
      (node (ref "C14") (pin "1") (pinfunction "1_1") (pintype "input"))
      (node (ref "D7") (pin "2") (pinfunction "A_2") (pintype "input"))
      (node (ref "FPC2") (pin "23") (pinfunction "23_23") (pintype "input"))
    )
    (net (code "20") (name "/RESE") (class "Default")
      (node (ref "FPC2") (pin "3") (pinfunction "3_3") (pintype "input"))
      (node (ref "Q3") (pin "2") (pinfunction "S_2") (pintype "input"))
      (node (ref "R14") (pin "2") (pinfunction "2_2") (pintype "input"))
    )
    (net (code "21") (name "/REST") (class "Default")
      (node (ref "FPC2") (pin "10") (pinfunction "10_10") (pintype "input"))
      (node (ref "U8") (pin "27") (pinfunction "IO16_27") (pintype "input"))
    )
    (net (code "22") (name "/RTS") (class "Default")
      (node (ref "Q5") (pin "3") (pinfunction "C_3") (pintype "input"))
      (node (ref "R8") (pin "1") (pinfunction "1_1") (pintype "input"))
      (node (ref "RESET1") (pin "1") (pinfunction "1_1") (pintype "input"))
      (node (ref "U8") (pin "3") (pinfunction "EN_3") (pintype "input"))
    )
    (net (code "23") (name "/RXD0") (class "Default")
      (node (ref "R11") (pin "1") (pinfunction "1_1") (pintype "input"))
      (node (ref "U4") (pin "2") (pinfunction "TXD_2") (pintype "input"))
      (node (ref "U8") (pin "34") (pinfunction "U0RXD_34") (pintype "input"))
    )
    (net (code "24") (name "/SCLK") (class "Default")
      (node (ref "CARD1") (pin "5") (pinfunction "CLX_5") (pintype "input"))
      (node (ref "FPC2") (pin "13") (pinfunction "13_13") (pintype "input"))
      (node (ref "R19") (pin "2") (pinfunction "2_2") (pintype "input"))
      (node (ref "U8") (pin "30") (pinfunction "IO18_30") (pintype "input"))
    )
    (net (code "25") (name "/SD_SS") (class "Default")
      (node (ref "CARD1") (pin "2") (pinfunction "CD/DAT3_2") (pintype "input"))
      (node (ref "R21") (pin "2") (pinfunction "2_2") (pintype "input"))
      (node (ref "U8") (pin "23") (pinfunction "IO15_23") (pintype "input"))
    )
    (net (code "26") (name "/TXD0") (class "Default")
      (node (ref "R10") (pin "1") (pinfunction "1_1") (pintype "input"))
      (node (ref "U4") (pin "3") (pinfunction "RXD_3") (pintype "input"))
      (node (ref "U8") (pin "35") (pinfunction "U0TXD_35") (pintype "input"))
    )
    (net (code "27") (name "3V3") (class "Default")
      (node (ref "C16") (pin "1") (pinfunction "1_1") (pintype "input"))
      (node (ref "C17") (pin "1") (pinfunction "1_1") (pintype "input"))
      (node (ref "C19") (pin "1") (pinfunction "1_1") (pintype "input"))
      (node (ref "C21") (pin "1") (pinfunction "1_1") (pintype "input"))
      (node (ref "C3") (pin "2") (pinfunction "2_2") (pintype "input"))
      (node (ref "C4") (pin "2") (pinfunction "2_2") (pintype "input"))
      (node (ref "CARD1") (pin "4") (pinfunction "VDD_4") (pintype "input"))
      (node (ref "FPC2") (pin "15") (pinfunction "15_15") (pintype "input"))
      (node (ref "FPC2") (pin "16") (pinfunction "16_16") (pintype "input"))
      (node (ref "L1") (pin "1") (pinfunction "1_1") (pintype "input"))
      (node (ref "R10") (pin "2") (pinfunction "2_2") (pintype "input"))
      (node (ref "R11") (pin "2") (pinfunction "2_2") (pintype "input"))
      (node (ref "R12") (pin "2") (pinfunction "2_2") (pintype "input"))
      (node (ref "R18") (pin "1") (pinfunction "1_1") (pintype "input"))
      (node (ref "R19") (pin "1") (pinfunction "1_1") (pintype "input"))
      (node (ref "R20") (pin "1") (pinfunction "1_1") (pintype "input"))
      (node (ref "R21") (pin "1") (pinfunction "1_1") (pintype "input"))
      (node (ref "R22") (pin "1") (pinfunction "1_1") (pintype "input"))
      (node (ref "R23") (pin "1") (pinfunction "1_1") (pintype "input"))
      (node (ref "R24") (pin "1") (pinfunction "1_1") (pintype "input"))
      (node (ref "R8") (pin "2") (pinfunction "2_2") (pintype "input"))
      (node (ref "R9") (pin "2") (pinfunction "2_2") (pintype "input"))
      (node (ref "S1") (pin "5") (pinfunction "VDD_5") (pintype "unspecified"))
      (node (ref "U2") (pin "5") (pinfunction "VOUT_5") (pintype "input"))
      (node (ref "U4") (pin "16") (pinfunction "VCC_16") (pintype "input"))
      (node (ref "U4") (pin "4") (pinfunction "V3_4") (pintype "input"))
      (node (ref "U8") (pin "2") (pinfunction "3V3_2") (pintype "input"))
    )
    (net (code "28") (name "GND") (class "Default")
      (node (ref "C1") (pin "1") (pinfunction "1_1") (pintype "input"))
      (node (ref "C10") (pin "2") (pinfunction "2_2") (pintype "input"))
      (node (ref "C11") (pin "2") (pinfunction "2_2") (pintype "input"))
      (node (ref "C12") (pin "2") (pinfunction "2_2") (pintype "input"))
      (node (ref "C13") (pin "2") (pinfunction "2_2") (pintype "input"))
      (node (ref "C14") (pin "2") (pinfunction "2_2") (pintype "input"))
      (node (ref "C15") (pin "2") (pinfunction "2_2") (pintype "input"))
      (node (ref "C16") (pin "2") (pinfunction "2_2") (pintype "input"))
      (node (ref "C17") (pin "2") (pinfunction "2_2") (pintype "input"))
      (node (ref "C19") (pin "2") (pinfunction "2_2") (pintype "input"))
      (node (ref "C2") (pin "1") (pinfunction "1_1") (pintype "input"))
      (node (ref "C20") (pin "2") (pinfunction "2_2") (pintype "input"))
      (node (ref "C21") (pin "2") (pinfunction "2_2") (pintype "input"))
      (node (ref "C22") (pin "2") (pinfunction "2_2") (pintype "input"))
      (node (ref "C23") (pin "2") (pinfunction "2_2") (pintype "input"))
      (node (ref "C24") (pin "2") (pinfunction "2_2") (pintype "input"))
      (node (ref "C3") (pin "1") (pinfunction "1_1") (pintype "input"))
      (node (ref "C4") (pin "1") (pinfunction "1_1") (pintype "input"))
      (node (ref "C5") (pin "1") (pinfunction "1_1") (pintype "input"))
      (node (ref "C6") (pin "1") (pinfunction "1_1") (pintype "input"))
      (node (ref "C7") (pin "2") (pinfunction "2_2") (pintype "input"))
      (node (ref "C8") (pin "2") (pinfunction "2_2") (pintype "input"))
      (node (ref "C9") (pin "2") (pinfunction "2_2") (pintype "input"))
      (node (ref "CARD1") (pin "10") (pinfunction "SHELL_10") (pintype "input"))
      (node (ref "CARD1") (pin "11") (pinfunction "SHELL_11") (pintype "input"))
      (node (ref "CARD1") (pin "12") (pinfunction "SHELL_12") (pintype "input"))
      (node (ref "CARD1") (pin "13") (pinfunction "SHELL_13") (pintype "input"))
      (node (ref "CARD1") (pin "6") (pinfunction "VSS_6") (pintype "input"))
      (node (ref "D1") (pin "1") (pinfunction "1_1") (pintype "input"))
      (node (ref "D6") (pin "1") (pinfunction "K_1") (pintype "input"))
      (node (ref "FPC2") (pin "17") (pinfunction "17_17") (pintype "input"))
      (node (ref "FPC2") (pin "25") (pinfunction "25_25") (pintype "input"))
      (node (ref "FPC2") (pin "26") (pinfunction "26_26") (pintype "input"))
      (node (ref "FPC2") (pin "8") (pinfunction "8_8") (pintype "input"))
      (node (ref "KEY1") (pin "1") (pinfunction "1_1") (pintype "input"))
      (node (ref "KEY1") (pin "3") (pinfunction "3_3") (pintype "input"))
      (node (ref "KEY1") (pin "4") (pinfunction "4_4") (pintype "input"))
      (node (ref "KEY2") (pin "1") (pinfunction "1_1") (pintype "input"))
      (node (ref "KEY2") (pin "3") (pinfunction "3_3") (pintype "input"))
      (node (ref "KEY2") (pin "4") (pinfunction "4_4") (pintype "input"))
      (node (ref "KEY3") (pin "1") (pinfunction "1_1") (pintype "input"))
      (node (ref "KEY3") (pin "3") (pinfunction "3_3") (pintype "input"))
      (node (ref "KEY3") (pin "4") (pinfunction "4_4") (pintype "input"))
      (node (ref "Q2") (pin "2") (pinfunction "S_2") (pintype "input"))
      (node (ref "Q7") (pin "2") (pinfunction "E_2") (pintype "input"))
      (node (ref "R1") (pin "1") (pinfunction "1_1") (pintype "input"))
      (node (ref "R13") (pin "1") (pinfunction "1_1") (pintype "input"))
      (node (ref "R14") (pin "1") (pinfunction "1_1") (pintype "input"))
      (node (ref "R16") (pin "1") (pinfunction "1_1") (pintype "input"))
      (node (ref "R2") (pin "1") (pinfunction "1_1") (pintype "input"))
      (node (ref "R3") (pin "1") (pinfunction "1_1") (pintype "input"))
      (node (ref "R5") (pin "1") (pinfunction "1_1") (pintype "input"))
      (node (ref "RESET1") (pin "2") (pinfunction "2_2") (pintype "input"))
      (node (ref "RESET1") (pin "3") (pinfunction "3_3") (pintype "input"))
      (node (ref "RESET1") (pin "4") (pinfunction "4_4") (pintype "input"))
      (node (ref "S1") (pin "2") (pinfunction "ADDR_2") (pintype "unspecified"))
      (node (ref "S1") (pin "7") (pinfunction "R_7") (pintype "unspecified"))
      (node (ref "S1") (pin "8") (pinfunction "VSS_8") (pintype "unspecified"))
      (node (ref "S1") (pin "9") (pinfunction "EPAD_9") (pintype "unspecified"))
      (node (ref "U1") (pin "1") (pinfunction "TEMP_1") (pintype "input"))
      (node (ref "U1") (pin "3") (pinfunction "GND_3") (pintype "input"))
      (node (ref "U1") (pin "9") (pinfunction "EP_9") (pintype "input"))
      (node (ref "U17") (pin "1") (pinfunction "1_1") (pintype "unspecified"))
      (node (ref "U17") (pin "2") (pinfunction "2_2") (pintype "unspecified"))
      (node (ref "U2") (pin "2") (pinfunction "VSS_2") (pintype "input"))
      (node (ref "U7") (pin "11") (pinfunction "GND_11") (pintype "input"))
      (node (ref "U7") (pin "7") (pinfunction "FOE_7") (pintype "input"))
      (node (ref "U8") (pin "1") (pinfunction "GND_1") (pintype "input"))
      (node (ref "U8") (pin "15") (pinfunction "GND_15") (pintype "input"))
      (node (ref "U8") (pin "38") (pinfunction "GND_38") (pintype "input"))
      (node (ref "U8") (pin "39") (pinfunction "EP_39") (pintype "input"))
      (node (ref "USB1") (pin "1") (pinfunction "SHELL_1") (pintype "input"))
      (node (ref "USB1") (pin "2") (pinfunction "SHELL_2") (pintype "input"))
      (node (ref "USB1") (pin "3") (pinfunction "SHELL_3") (pintype "input"))
      (node (ref "USB1") (pin "4") (pinfunction "SHELL_4") (pintype "input"))
      (node (ref "USB1") (pin "A1B12") (pinfunction "GND_A1B12") (pintype "input"))
      (node (ref "USB1") (pin "B1A12") (pinfunction "GND_B1A12") (pintype "input"))
    )
    (net (code "29") (name "Net-(BUZZER1-Pad1)") (class "Default")
      (node (ref "BUZZER1") (pin "1") (pinfunction "1_1") (pintype "input"))
      (node (ref "R17") (pin "2") (pinfunction "2_2") (pintype "input"))
    )
    (net (code "30") (name "Net-(C7-Pad1)") (class "Default")
      (node (ref "C7") (pin "1") (pinfunction "1_1") (pintype "input"))
      (node (ref "FPC2") (pin "4") (pinfunction "4_4") (pintype "input"))
    )
    (net (code "31") (name "Net-(C8-Pad1)") (class "Default")
      (node (ref "C8") (pin "1") (pinfunction "1_1") (pintype "input"))
      (node (ref "FPC2") (pin "5") (pinfunction "5_5") (pintype "input"))
    )
    (net (code "32") (name "Net-(C9-Pad1)") (class "Default")
      (node (ref "C9") (pin "1") (pinfunction "1_1") (pintype "input"))
      (node (ref "FPC2") (pin "18") (pinfunction "18_18") (pintype "input"))
    )
    (net (code "33") (name "Net-(C10-Pad1)") (class "Default")
      (node (ref "C10") (pin "1") (pinfunction "1_1") (pintype "input"))
      (node (ref "FPC2") (pin "19") (pinfunction "19_19") (pintype "input"))
    )
    (net (code "34") (name "Net-(C11-Pad1)") (class "Default")
      (node (ref "C11") (pin "1") (pinfunction "1_1") (pintype "input"))
      (node (ref "FPC2") (pin "20") (pinfunction "20_20") (pintype "input"))
    )
    (net (code "35") (name "Net-(C13-Pad1)") (class "Default")
      (node (ref "C13") (pin "1") (pinfunction "1_1") (pintype "input"))
      (node (ref "FPC2") (pin "22") (pinfunction "22_22") (pintype "input"))
    )
    (net (code "36") (name "Net-(C15-Pad1)") (class "Default")
      (node (ref "C15") (pin "1") (pinfunction "1_1") (pintype "input"))
      (node (ref "FPC2") (pin "24") (pinfunction "24_24") (pintype "input"))
    )
    (net (code "37") (name "Net-(CHRG1-A)") (class "Default")
      (node (ref "CHRG1") (pin "1") (pinfunction "A_1") (pintype "input"))
      (node (ref "DONE1") (pin "1") (pinfunction "A_1") (pintype "input"))
      (node (ref "R4") (pin "1") (pinfunction "1_1") (pintype "input"))
    )
    (net (code "38") (name "Net-(CHRG1-C)") (class "Default")
      (node (ref "CHRG1") (pin "2") (pinfunction "C_2") (pintype "input"))
      (node (ref "U1") (pin "7") (pinfunction "CHRG_7") (pintype "input"))
    )
    (net (code "39") (name "Net-(D4-C)") (class "Default")
      (node (ref "C2") (pin "2") (pinfunction "2_2") (pintype "input"))
      (node (ref "D4") (pin "1") (pinfunction "C_1") (pintype "input"))
      (node (ref "Q1") (pin "2") (pinfunction "S_2") (pintype "input"))
      (node (ref "U2") (pin "1") (pinfunction "VIN_1") (pintype "input"))
      (node (ref "U2") (pin "3") (pinfunction "CE_3") (pintype "input"))
    )
    (net (code "40") (name "Net-(D5-K)") (class "Default")
      (node (ref "C5") (pin "2") (pinfunction "2_2") (pintype "input"))
      (node (ref "C6") (pin "2") (pinfunction "2_2") (pintype "input"))
      (node (ref "D5") (pin "1") (pinfunction "K_1") (pintype "input"))
      (node (ref "U7") (pin "6") (pinfunction "VDD_6") (pintype "input"))
    )
    (net (code "41") (name "Net-(D6-A)") (class "Default")
      (node (ref "C18") (pin "1") (pinfunction "1_1") (pintype "input"))
      (node (ref "D6") (pin "2") (pinfunction "A_2") (pintype "input"))
      (node (ref "D7") (pin "1") (pinfunction "K_1") (pintype "input"))
    )
    (net (code "42") (name "Net-(D8-A)") (class "Default")
      (node (ref "C18") (pin "2") (pinfunction "2_2") (pintype "input"))
      (node (ref "D8") (pin "2") (pinfunction "A_2") (pintype "input"))
      (node (ref "L1") (pin "2") (pinfunction "2_2") (pintype "input"))
      (node (ref "Q3") (pin "3") (pinfunction "D_3") (pintype "input"))
    )
    (net (code "43") (name "Net-(DONE1-C)") (class "Default")
      (node (ref "DONE1") (pin "2") (pinfunction "C_2") (pintype "input"))
      (node (ref "U1") (pin "6") (pinfunction "STDBY_6") (pintype "input"))
    )
    (net (code "44") (name "Net-(Q2-D)") (class "Default")
      (node (ref "Q2") (pin "3") (pinfunction "D_3") (pintype "input"))
      (node (ref "U4") (pin "1") (pinfunction "GND_1") (pintype "input"))
    )
    (net (code "45") (name "Net-(Q4-B)") (class "Default")
      (node (ref "Q4") (pin "1") (pinfunction "B_1") (pintype "input"))
      (node (ref "R7") (pin "1") (pinfunction "1_1") (pintype "input"))
    )
    (net (code "46") (name "Net-(Q4-E)") (class "Default")
      (node (ref "Q4") (pin "2") (pinfunction "E_2") (pintype "input"))
      (node (ref "R6") (pin "2") (pinfunction "2_2") (pintype "input"))
      (node (ref "U4") (pin "13") (pinfunction "DTR#_13") (pintype "input"))
    )
    (net (code "47") (name "Net-(Q5-B)") (class "Default")
      (node (ref "Q5") (pin "1") (pinfunction "B_1") (pintype "input"))
      (node (ref "R6") (pin "1") (pinfunction "1_1") (pintype "input"))
    )
    (net (code "48") (name "Net-(Q5-E)") (class "Default")
      (node (ref "Q5") (pin "2") (pinfunction "E_2") (pintype "input"))
      (node (ref "R7") (pin "2") (pinfunction "2_2") (pintype "input"))
      (node (ref "U4") (pin "14") (pinfunction "RTS#_14") (pintype "input"))
    )
    (net (code "49") (name "Net-(Q7-B)") (class "Default")
      (node (ref "Q7") (pin "1") (pinfunction "B_1") (pintype "input"))
      (node (ref "R15") (pin "1") (pinfunction "1_1") (pintype "input"))
      (node (ref "R16") (pin "2") (pinfunction "2_2") (pintype "input"))
    )
    (net (code "50") (name "Net-(Q7-C)") (class "Default")
      (node (ref "BUZZER1") (pin "2") (pinfunction "2_2") (pintype "input"))
      (node (ref "Q7") (pin "3") (pinfunction "C_3") (pintype "input"))
    )
    (net (code "51") (name "Net-(U1-PROG)") (class "Default")
      (node (ref "R3") (pin "2") (pinfunction "2_2") (pintype "input"))
      (node (ref "U1") (pin "2") (pinfunction "PROG_2") (pintype "input"))
    )
    (net (code "52") (name "Net-(USB1-CC1)") (class "Default")
      (node (ref "R1") (pin "2") (pinfunction "2_2") (pintype "input"))
      (node (ref "USB1") (pin "A5") (pinfunction "CC1_A5") (pintype "input"))
      (node (ref "USB1") (pin "B5") (pinfunction "CC2_B5") (pintype "input"))
    )
    (net (code "53") (name "unconnected-(CARD1-CD-Pad9)") (class "Default")
      (node (ref "CARD1") (pin "9") (pinfunction "CD_9") (pintype "input+no_connect"))
    )
    (net (code "54") (name "unconnected-(CARD1-DAT1-Pad8)") (class "Default")
      (node (ref "CARD1") (pin "8") (pinfunction "DAT1_8") (pintype "input+no_connect"))
    )
    (net (code "55") (name "unconnected-(CARD1-DAT2-Pad1)") (class "Default")
      (node (ref "CARD1") (pin "1") (pinfunction "DAT2_1") (pintype "input+no_connect"))
    )
    (net (code "56") (name "unconnected-(FPC2-Pad1)") (class "Default")
      (node (ref "FPC2") (pin "1") (pinfunction "1_1") (pintype "input+no_connect"))
    )
    (net (code "57") (name "unconnected-(FPC2-Pad6)") (class "Default")
      (node (ref "FPC2") (pin "6") (pinfunction "6_6") (pintype "input+no_connect"))
    )
    (net (code "58") (name "unconnected-(FPC2-Pad7)") (class "Default")
      (node (ref "FPC2") (pin "7") (pinfunction "7_7") (pintype "input+no_connect"))
    )
    (net (code "59") (name "unconnected-(S1-ALERT-Pad3)") (class "Default")
      (node (ref "S1") (pin "3") (pinfunction "ALERT_3") (pintype "unspecified+no_connect"))
    )
    (net (code "60") (name "unconnected-(S1-NRESET-Pad6)") (class "Default")
      (node (ref "S1") (pin "6") (pinfunction "NRESET_6") (pintype "unspecified+no_connect"))
    )
    (net (code "61") (name "unconnected-(U2-NC-Pad4)") (class "Default")
      (node (ref "U2") (pin "4") (pinfunction "NC_4") (pintype "input+no_connect"))
    )
    (net (code "62") (name "unconnected-(U4-CTS#-Pad9)") (class "Default")
      (node (ref "U4") (pin "9") (pinfunction "CTS#_9") (pintype "input+no_connect"))
    )
    (net (code "63") (name "unconnected-(U4-DCD#-Pad12)") (class "Default")
      (node (ref "U4") (pin "12") (pinfunction "DCD#_12") (pintype "input+no_connect"))
    )
    (net (code "64") (name "unconnected-(U4-DSR#-Pad10)") (class "Default")
      (node (ref "U4") (pin "10") (pinfunction "DSR#_10") (pintype "input+no_connect"))
    )
    (net (code "65") (name "unconnected-(U4-NC.-Pad7)") (class "Default")
      (node (ref "U4") (pin "7") (pinfunction "NC._7") (pintype "input+no_connect"))
    )
    (net (code "66") (name "unconnected-(U4-NC.-Pad8)") (class "Default")
      (node (ref "U4") (pin "8") (pinfunction "NC._8") (pintype "input+no_connect"))
    )
    (net (code "67") (name "unconnected-(U4-R232-Pad15)") (class "Default")
      (node (ref "U4") (pin "15") (pinfunction "R232_15") (pintype "input+no_connect"))
    )
    (net (code "68") (name "unconnected-(U4-RI#-Pad11)") (class "Default")
      (node (ref "U4") (pin "11") (pinfunction "RI#_11") (pintype "input+no_connect"))
    )
    (net (code "69") (name "unconnected-(U7-FOUT-Pad3)") (class "Default")
      (node (ref "U7") (pin "3") (pinfunction "FOUT_3") (pintype "input+no_connect"))
    )
    (net (code "70") (name "unconnected-(U7-INT#-Pad10)") (class "Default")
      (node (ref "U7") (pin "10") (pinfunction "INT#_10") (pintype "input+no_connect"))
    )
    (net (code "71") (name "unconnected-(U7-NC-Pad4)") (class "Default")
      (node (ref "U7") (pin "4") (pinfunction "NC_4") (pintype "input+no_connect"))
    )
    (net (code "72") (name "unconnected-(U7-NC-Pad8)") (class "Default")
      (node (ref "U7") (pin "8") (pinfunction "NC_8") (pintype "input+no_connect"))
    )
    (net (code "73") (name "unconnected-(U7-NC-Pad9)") (class "Default")
      (node (ref "U7") (pin "9") (pinfunction "NC_9") (pintype "input+no_connect"))
    )
    (net (code "74") (name "unconnected-(U7-NC-Pad14)") (class "Default")
      (node (ref "U7") (pin "14") (pinfunction "NC_14") (pintype "input+no_connect"))
    )
    (net (code "75") (name "unconnected-(U7-T1-Pad1)") (class "Default")
      (node (ref "U7") (pin "1") (pinfunction "T1_1") (pintype "input+no_connect"))
    )
    (net (code "76") (name "unconnected-(U7-T2-Pad12)") (class "Default")
      (node (ref "U7") (pin "12") (pinfunction "T2_12") (pintype "input+no_connect"))
    )
    (net (code "77") (name "unconnected-(U7-TEST-Pad5)") (class "Default")
      (node (ref "U7") (pin "5") (pinfunction "TEST_5") (pintype "input+no_connect"))
    )
    (net (code "78") (name "unconnected-(U8-CLK-Pad20)") (class "Default")
      (node (ref "U8") (pin "20") (pinfunction "CLK_20") (pintype "input+no_connect"))
    )
    (net (code "79") (name "unconnected-(U8-CMD-Pad19)") (class "Default")
      (node (ref "U8") (pin "19") (pinfunction "CMD_19") (pintype "input+no_connect"))
    )
    (net (code "80") (name "unconnected-(U8-IO2-Pad24)") (class "Default")
      (node (ref "U8") (pin "24") (pinfunction "IO2_24") (pintype "input+no_connect"))
    )
    (net (code "81") (name "unconnected-(U8-IO12-Pad14)") (class "Default")
      (node (ref "U8") (pin "14") (pinfunction "IO12_14") (pintype "input+no_connect"))
    )
    (net (code "82") (name "unconnected-(U8-IO13-Pad16)") (class "Default")
      (node (ref "U8") (pin "16") (pinfunction "IO13_16") (pintype "input+no_connect"))
    )
    (net (code "83") (name "unconnected-(U8-IO14-Pad13)") (class "Default")
      (node (ref "U8") (pin "13") (pinfunction "IO14_13") (pintype "input+no_connect"))
    )
    (net (code "84") (name "unconnected-(U8-IO32-Pad8)") (class "Default")
      (node (ref "U8") (pin "8") (pinfunction "IO32_8") (pintype "input+no_connect"))
    )
    (net (code "85") (name "unconnected-(U8-IO34-Pad6)") (class "Default")
      (node (ref "U8") (pin "6") (pinfunction "IO34_6") (pintype "input+no_connect"))
    )
    (net (code "86") (name "unconnected-(U8-IO35-Pad7)") (class "Default")
      (node (ref "U8") (pin "7") (pinfunction "IO35_7") (pintype "input+no_connect"))
    )
    (net (code "87") (name "unconnected-(U8-NC-Pad32)") (class "Default")
      (node (ref "U8") (pin "32") (pinfunction "NC_32") (pintype "input+no_connect"))
    )
    (net (code "88") (name "unconnected-(U8-SD2-Pad17)") (class "Default")
      (node (ref "U8") (pin "17") (pinfunction "SD2_17") (pintype "input+no_connect"))
    )
    (net (code "89") (name "unconnected-(U8-SD3-Pad18)") (class "Default")
      (node (ref "U8") (pin "18") (pinfunction "SD3_18") (pintype "input+no_connect"))
    )
    (net (code "90") (name "unconnected-(U8-SDI-Pad22)") (class "Default")
      (node (ref "U8") (pin "22") (pinfunction "SDI_22") (pintype "input+no_connect"))
    )
    (net (code "91") (name "unconnected-(U8-SDO-Pad21)") (class "Default")
      (node (ref "U8") (pin "21") (pinfunction "SDO_21") (pintype "input+no_connect"))
    )
    (net (code "92") (name "unconnected-(U8-SENSOR_VN-Pad5)") (class "Default")
      (node (ref "U8") (pin "5") (pinfunction "SENSOR_VN_5") (pintype "input+no_connect"))
    )
    (net (code "93") (name "unconnected-(U8-SENSOR_VP-Pad4)") (class "Default")
      (node (ref "U8") (pin "4") (pinfunction "SENSOR_VP_4") (pintype "input+no_connect"))
    )
    (net (code "94") (name "unconnected-(USB1-SBU1-PadA8)") (class "Default")
      (node (ref "USB1") (pin "A8") (pinfunction "SBU1_A8") (pintype "input+no_connect"))
    )
    (net (code "95") (name "unconnected-(USB1-SBU2-PadB8)") (class "Default")
      (node (ref "USB1") (pin "B8") (pinfunction "SBU2_B8") (pintype "input+no_connect"))
    )
  )
)
